# board.net
KiCad netlist of a schematic drawn in EAGLE
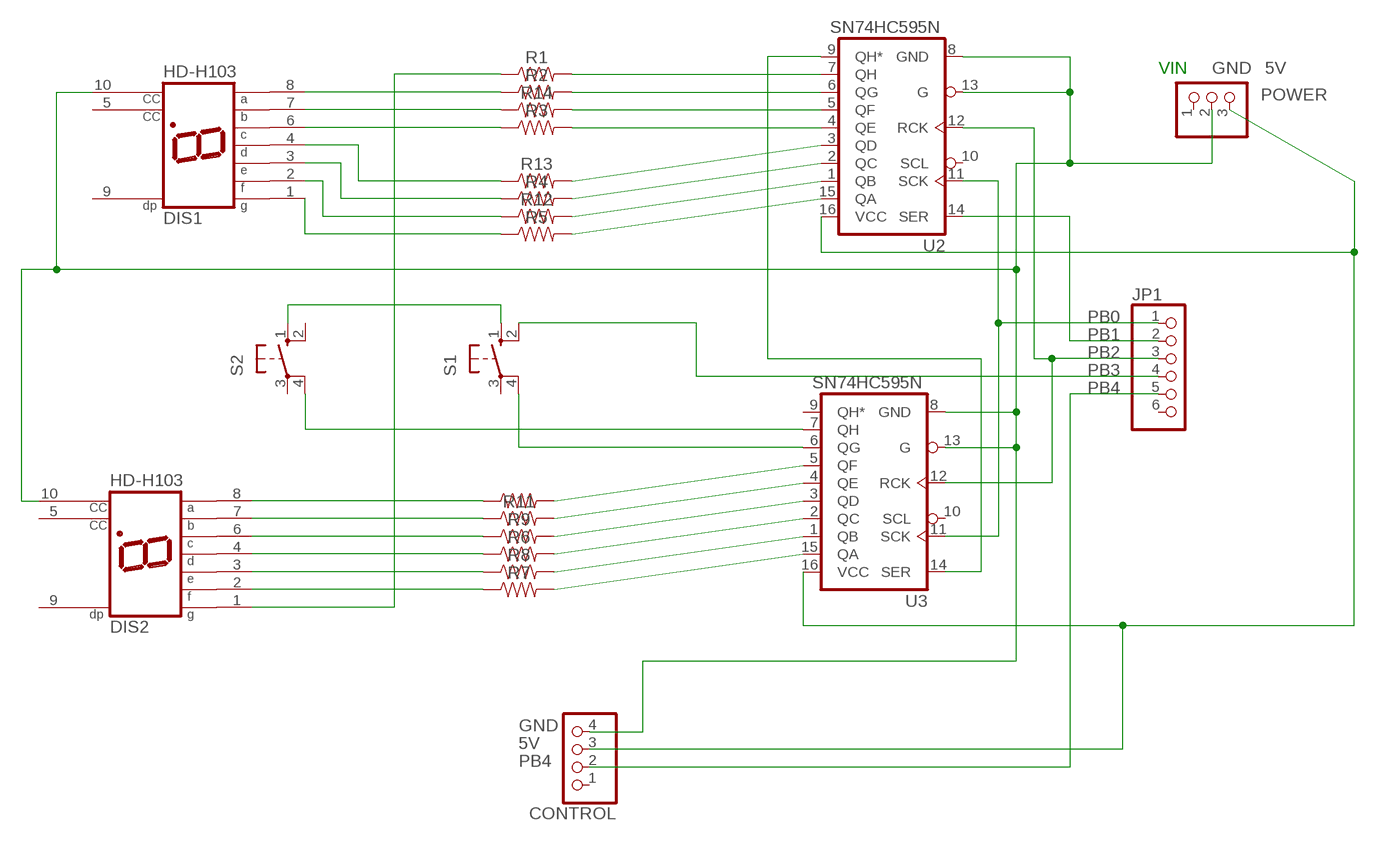
[diagram p0: schematic, sheet 1]

(export (version "E")
  (design (tool "Eeschema 10.0.6"))
  (components
    (comp (ref "CONTROL")
      (value "PINHD-1X4")
      (footprint "eagle-import:1X04")
      (libsource (lib "eagle-import") (part "PINHD-1X4"))
    )
    (comp (ref "DIS1")
      (value "HD-H103")
      (footprint "eagle-import:HDSP-M")
      (libsource (lib "eagle-import") (part "HD-H103"))
    )
    (comp (ref "DIS2")
      (value "HD-H103")
      (footprint "eagle-import:HDSP-M")
      (libsource (lib "eagle-import") (part "HD-H103"))
    )
    (comp (ref "JP1")
      (value "PINHD-1X6")
      (footprint "eagle-import:1X06")
      (libsource (lib "eagle-import") (part "PINHD-1X6"))
    )
    (comp (ref "POWER")
      (value "PINHD-1X3")
      (footprint "eagle-import:1X03")
      (libsource (lib "eagle-import") (part "PINHD-1X3"))
    )
    (comp (ref "R1")
      (value "RESISTORAXIAL-0.3")
      (footprint "eagle-import:AXIAL-0.3")
      (libsource (lib "eagle-import") (part "RESISTORAXIAL-0.3"))
    )
    (comp (ref "R2")
      (value "RESISTORAXIAL-0.3")
      (footprint "eagle-import:AXIAL-0.3")
      (libsource (lib "eagle-import") (part "RESISTORAXIAL-0.3"))
    )
    (comp (ref "R3")
      (value "RESISTORAXIAL-0.3")
      (footprint "eagle-import:AXIAL-0.3")
      (libsource (lib "eagle-import") (part "RESISTORAXIAL-0.3"))
    )
    (comp (ref "R4")
      (value "RESISTORAXIAL-0.3")
      (footprint "eagle-import:AXIAL-0.3")
      (libsource (lib "eagle-import") (part "RESISTORAXIAL-0.3"))
    )
    (comp (ref "R5")
      (value "RESISTORAXIAL-0.3")
      (footprint "eagle-import:AXIAL-0.3")
      (libsource (lib "eagle-import") (part "RESISTORAXIAL-0.3"))
    )
    (comp (ref "R6")
      (value "RESISTORAXIAL-0.3")
      (footprint "eagle-import:AXIAL-0.3")
      (libsource (lib "eagle-import") (part "RESISTORAXIAL-0.3"))
    )
    (comp (ref "R7")
      (value "RESISTORAXIAL-0.3")
      (footprint "eagle-import:AXIAL-0.3")
      (libsource (lib "eagle-import") (part "RESISTORAXIAL-0.3"))
    )
    (comp (ref "R8")
      (value "RESISTORAXIAL-0.3")
      (footprint "eagle-import:AXIAL-0.3")
      (libsource (lib "eagle-import") (part "RESISTORAXIAL-0.3"))
    )
    (comp (ref "R9")
      (value "RESISTORAXIAL-0.3")
      (footprint "eagle-import:AXIAL-0.3")
      (libsource (lib "eagle-import") (part "RESISTORAXIAL-0.3"))
    )
    (comp (ref "R11")
      (value "RESISTORAXIAL-0.3")
      (footprint "eagle-import:AXIAL-0.3")
      (libsource (lib "eagle-import") (part "RESISTORAXIAL-0.3"))
    )
    (comp (ref "R12")
      (value "RESISTORAXIAL-0.3")
      (footprint "eagle-import:AXIAL-0.3")
      (libsource (lib "eagle-import") (part "RESISTORAXIAL-0.3"))
    )
    (comp (ref "R13")
      (value "RESISTORAXIAL-0.3")
      (footprint "eagle-import:AXIAL-0.3")
      (libsource (lib "eagle-import") (part "RESISTORAXIAL-0.3"))
    )
    (comp (ref "R14")
      (value "RESISTORAXIAL-0.3")
      (footprint "eagle-import:AXIAL-0.3")
      (libsource (lib "eagle-import") (part "RESISTORAXIAL-0.3"))
    )
    (comp (ref "R15")
      (value "RESISTORAXIAL-0.3")
      (footprint "eagle-import:AXIAL-0.3")
      (libsource (lib "eagle-import") (part "RESISTORAXIAL-0.3"))
    )
    (comp (ref "S1")
      (value "40-XX")
      (footprint "eagle-import:B3F-40XX")
      (fields (field (name "MF") "OMRON COMPONENTS USA") (field (name "MPN") "B3F-4000"))
      (libsource (lib "eagle-import") (part "40-XX"))
    )
    (comp (ref "S2")
      (value "40-XX")
      (footprint "eagle-import:B3F-40XX")
      (fields (field (name "MF") "OMRON COMPONENTS USA") (field (name "MPN") "B3F-4000"))
      (libsource (lib "eagle-import") (part "40-XX"))
    )
    (comp (ref "U2")
      (value "SN74HC595N")
      (footprint "eagle-import:DIP16")
      (libsource (lib "eagle-import") (part "74595NHC"))
    )
    (comp (ref "U3")
      (value "SN74HC595N")
      (footprint "eagle-import:DIP16")
      (libsource (lib "eagle-import") (part "74595NHC"))
    )
  )
  (nets
    (net (code "1") (name "/5V") (class "Default")
      (node (ref "CONTROL") (pin "3") (pinfunction "3_3") (pintype "passive"))
      (node (ref "POWER") (pin "3") (pinfunction "3_3") (pintype "passive"))
      (node (ref "U2") (pin "16") (pinfunction "VCC_16") (pintype "power_in"))
      (node (ref "U3") (pin "16") (pinfunction "VCC_16") (pintype "power_in"))
    )
    (net (code "2") (name "/GND") (class "Default")
      (node (ref "CONTROL") (pin "4") (pinfunction "4_4") (pintype "passive"))
      (node (ref "DIS1") (pin "10") (pinfunction "CC_10") (pintype "passive"))
      (node (ref "DIS2") (pin "10") (pinfunction "CC_10") (pintype "passive"))
      (node (ref "POWER") (pin "2") (pinfunction "2_2") (pintype "passive"))
      (node (ref "U2") (pin "13") (pinfunction "G_13") (pintype "input"))
      (node (ref "U2") (pin "8") (pinfunction "GND_8") (pintype "power_in"))
      (node (ref "U3") (pin "13") (pinfunction "G_13") (pintype "input"))
      (node (ref "U3") (pin "8") (pinfunction "GND_8") (pintype "power_in"))
    )
    (net (code "3") (name "/PB0") (class "Default")
      (node (ref "JP1") (pin "1") (pinfunction "1_1") (pintype "passive"))
      (node (ref "U2") (pin "11") (pinfunction "SCK_11") (pintype "input"))
      (node (ref "U3") (pin "11") (pinfunction "SCK_11") (pintype "input"))
    )
    (net (code "4") (name "/PB1") (class "Default")
      (node (ref "JP1") (pin "2") (pinfunction "2_2") (pintype "passive"))
      (node (ref "U2") (pin "14") (pinfunction "SER_14") (pintype "input"))
    )
    (net (code "5") (name "/PB2") (class "Default")
      (node (ref "JP1") (pin "3") (pinfunction "3_3") (pintype "passive"))
      (node (ref "U2") (pin "12") (pinfunction "RCK_12") (pintype "input"))
      (node (ref "U3") (pin "12") (pinfunction "RCK_12") (pintype "input"))
    )
    (net (code "6") (name "/PB3") (class "Default")
      (node (ref "JP1") (pin "4") (pinfunction "4_4") (pintype "passive"))
      (node (ref "S1") (pin "2") (pinfunction "S1_2") (pintype "passive"))
    )
    (net (code "7") (name "/PB4") (class "Default")
      (node (ref "CONTROL") (pin "2") (pinfunction "2_2") (pintype "passive"))
      (node (ref "JP1") (pin "5") (pinfunction "5_5") (pintype "passive"))
    )
    (net (code "8") (name "Net-(DIS1-A)") (class "Default")
      (node (ref "DIS1") (pin "3") (pinfunction "A_3") (pintype "passive"))
      (node (ref "R4") (pin "P$1") (pinfunction "1_P$1") (pintype "passive"))
    )
    (net (code "9") (name "Net-(DIS1-B)") (class "Default")
      (node (ref "DIS1") (pin "4") (pinfunction "B_4") (pintype "passive"))
      (node (ref "R13") (pin "P$1") (pinfunction "1_P$1") (pintype "passive"))
    )
    (net (code "10") (name "Net-(DIS1-C)") (class "Default")
      (node (ref "DIS1") (pin "8") (pinfunction "C_8") (pintype "passive"))
      (node (ref "R2") (pin "P$1") (pinfunction "1_P$1") (pintype "passive"))
    )
    (net (code "11") (name "Net-(DIS1-D)") (class "Default")
      (node (ref "DIS1") (pin "7") (pinfunction "D_7") (pintype "passive"))
      (node (ref "R14") (pin "P$1") (pinfunction "1_P$1") (pintype "passive"))
    )
    (net (code "12") (name "Net-(DIS1-E)") (class "Default")
      (node (ref "DIS1") (pin "6") (pinfunction "E_6") (pintype "passive"))
      (node (ref "R3") (pin "P$1") (pinfunction "1_P$1") (pintype "passive"))
    )
    (net (code "13") (name "Net-(DIS1-F)") (class "Default")
      (node (ref "DIS1") (pin "1") (pinfunction "F_1") (pintype "passive"))
      (node (ref "R5") (pin "P$1") (pinfunction "1_P$1") (pintype "passive"))
    )
    (net (code "14") (name "Net-(DIS1-G)") (class "Default")
      (node (ref "DIS1") (pin "2") (pinfunction "G_2") (pintype "passive"))
      (node (ref "R12") (pin "P$1") (pinfunction "1_P$1") (pintype "passive"))
    )
    (net (code "15") (name "Net-(DIS2-A)") (class "Default")
      (node (ref "DIS2") (pin "3") (pinfunction "A_3") (pintype "passive"))
      (node (ref "R8") (pin "P$1") (pinfunction "1_P$1") (pintype "passive"))
    )
    (net (code "16") (name "Net-(DIS2-B)") (class "Default")
      (node (ref "DIS2") (pin "4") (pinfunction "B_4") (pintype "passive"))
      (node (ref "R6") (pin "P$1") (pinfunction "1_P$1") (pintype "passive"))
    )
    (net (code "17") (name "Net-(DIS2-C)") (class "Default")
      (node (ref "DIS2") (pin "8") (pinfunction "C_8") (pintype "passive"))
      (node (ref "R15") (pin "P$1") (pinfunction "1_P$1") (pintype "passive"))
    )
    (net (code "18") (name "Net-(DIS2-D)") (class "Default")
      (node (ref "DIS2") (pin "7") (pinfunction "D_7") (pintype "passive"))
      (node (ref "R11") (pin "P$1") (pinfunction "1_P$1") (pintype "passive"))
    )
    (net (code "19") (name "Net-(DIS2-E)") (class "Default")
      (node (ref "DIS2") (pin "6") (pinfunction "E_6") (pintype "passive"))
      (node (ref "R9") (pin "P$1") (pinfunction "1_P$1") (pintype "passive"))
    )
    (net (code "20") (name "Net-(DIS2-F)") (class "Default")
      (node (ref "DIS2") (pin "1") (pinfunction "F_1") (pintype "passive"))
      (node (ref "R1") (pin "P$1") (pinfunction "1_P$1") (pintype "passive"))
    )
    (net (code "21") (name "Net-(DIS2-G)") (class "Default")
      (node (ref "DIS2") (pin "2") (pinfunction "G_2") (pintype "passive"))
      (node (ref "R7") (pin "P$1") (pinfunction "1_P$1") (pintype "passive"))
    )
    (net (code "22") (name "Net-(R1-2)") (class "Default")
      (node (ref "R1") (pin "P$2") (pinfunction "2_P$2") (pintype "passive"))
      (node (ref "U2") (pin "7") (pinfunction "QH_7") (pintype "tri_state"))
    )
    (net (code "23") (name "Net-(R2-2)") (class "Default")
      (node (ref "R2") (pin "P$2") (pinfunction "2_P$2") (pintype "passive"))
      (node (ref "U2") (pin "6") (pinfunction "QG_6") (pintype "tri_state"))
    )
    (net (code "24") (name "Net-(R3-2)") (class "Default")
      (node (ref "R3") (pin "P$2") (pinfunction "2_P$2") (pintype "passive"))
      (node (ref "U2") (pin "4") (pinfunction "QE_4") (pintype "tri_state"))
    )
    (net (code "25") (name "Net-(R4-2)") (class "Default")
      (node (ref "R4") (pin "P$2") (pinfunction "2_P$2") (pintype "passive"))
      (node (ref "U2") (pin "2") (pinfunction "QC_2") (pintype "tri_state"))
    )
    (net (code "26") (name "Net-(R5-2)") (class "Default")
      (node (ref "R5") (pin "P$2") (pinfunction "2_P$2") (pintype "passive"))
      (node (ref "U2") (pin "15") (pinfunction "QA_15") (pintype "tri_state"))
    )
    (net (code "27") (name "Net-(R6-2)") (class "Default")
      (node (ref "R6") (pin "P$2") (pinfunction "2_P$2") (pintype "passive"))
      (node (ref "U3") (pin "2") (pinfunction "QC_2") (pintype "tri_state"))
    )
    (net (code "28") (name "Net-(R7-2)") (class "Default")
      (node (ref "R7") (pin "P$2") (pinfunction "2_P$2") (pintype "passive"))
      (node (ref "U3") (pin "15") (pinfunction "QA_15") (pintype "tri_state"))
    )
    (net (code "29") (name "Net-(R8-2)") (class "Default")
      (node (ref "R8") (pin "P$2") (pinfunction "2_P$2") (pintype "passive"))
      (node (ref "U3") (pin "1") (pinfunction "QB_1") (pintype "tri_state"))
    )
    (net (code "30") (name "Net-(R9-2)") (class "Default")
      (node (ref "R9") (pin "P$2") (pinfunction "2_P$2") (pintype "passive"))
      (node (ref "U3") (pin "3") (pinfunction "QD_3") (pintype "tri_state"))
    )
    (net (code "31") (name "Net-(R11-2)") (class "Default")
      (node (ref "R11") (pin "P$2") (pinfunction "2_P$2") (pintype "passive"))
      (node (ref "U3") (pin "4") (pinfunction "QE_4") (pintype "tri_state"))
    )
    (net (code "32") (name "Net-(R12-2)") (class "Default")
      (node (ref "R12") (pin "P$2") (pinfunction "2_P$2") (pintype "passive"))
      (node (ref "U2") (pin "1") (pinfunction "QB_1") (pintype "tri_state"))
    )
    (net (code "33") (name "Net-(R13-2)") (class "Default")
      (node (ref "R13") (pin "P$2") (pinfunction "2_P$2") (pintype "passive"))
      (node (ref "U2") (pin "3") (pinfunction "QD_3") (pintype "tri_state"))
    )
    (net (code "34") (name "Net-(R14-2)") (class "Default")
      (node (ref "R14") (pin "P$2") (pinfunction "2_P$2") (pintype "passive"))
      (node (ref "U2") (pin "5") (pinfunction "QF_5") (pintype "tri_state"))
    )
    (net (code "35") (name "Net-(R15-2)") (class "Default")
      (node (ref "R15") (pin "P$2") (pinfunction "2_P$2") (pintype "passive"))
      (node (ref "U3") (pin "5") (pinfunction "QF_5") (pintype "tri_state"))
    )
    (net (code "36") (name "Net-(S1-P1)") (class "Default")
      (node (ref "S1") (pin "4") (pinfunction "P1_4") (pintype "passive"))
      (node (ref "U3") (pin "6") (pinfunction "QG_6") (pintype "tri_state"))
    )
    (net (code "37") (name "Net-(S1-S)") (class "Default")
      (node (ref "S1") (pin "1") (pinfunction "S_1") (pintype "passive"))
      (node (ref "S2") (pin "1") (pinfunction "S_1") (pintype "passive"))
    )
    (net (code "38") (name "Net-(S2-P1)") (class "Default")
      (node (ref "S2") (pin "4") (pinfunction "P1_4") (pintype "passive"))
      (node (ref "U3") (pin "7") (pinfunction "QH_7") (pintype "tri_state"))
    )
    (net (code "39") (name "Net-(U2-QH*)") (class "Default")
      (node (ref "U2") (pin "9") (pinfunction "QH*_9") (pintype "tri_state"))
      (node (ref "U3") (pin "14") (pinfunction "SER_14") (pintype "input"))
    )
    (net (code "40") (name "unconnected-(CONTROL-Pad1)") (class "Default")
      (node (ref "CONTROL") (pin "1") (pinfunction "1_1") (pintype "passive"))
    )
    (net (code "41") (name "unconnected-(DIS1-CC-Pad5)") (class "Default")
      (node (ref "DIS1") (pin "5") (pinfunction "CC_5") (pintype "passive"))
    )
    (net (code "42") (name "unconnected-(DIS1-DP-Pad9)") (class "Default")
      (node (ref "DIS1") (pin "9") (pinfunction "DP_9") (pintype "passive"))
    )
    (net (code "43") (name "unconnected-(DIS2-CC-Pad5)") (class "Default")
      (node (ref "DIS2") (pin "5") (pinfunction "CC_5") (pintype "passive"))
    )
    (net (code "44") (name "unconnected-(DIS2-DP-Pad9)") (class "Default")
      (node (ref "DIS2") (pin "9") (pinfunction "DP_9") (pintype "passive"))
    )
    (net (code "45") (name "unconnected-(JP1-Pad6)") (class "Default")
      (node (ref "JP1") (pin "6") (pinfunction "6_6") (pintype "passive"))
    )
    (net (code "46") (name "unconnected-(POWER-Pad1)") (class "Default")
      (node (ref "POWER") (pin "1") (pinfunction "1_1") (pintype "passive"))
    )
    (net (code "47") (name "unconnected-(S1-P-Pad3)") (class "Default")
      (node (ref "S1") (pin "3") (pinfunction "P_3") (pintype "passive"))
    )
    (net (code "48") (name "unconnected-(S2-P-Pad3)") (class "Default")
      (node (ref "S2") (pin "3") (pinfunction "P_3") (pintype "passive"))
    )
    (net (code "49") (name "unconnected-(S2-S1-Pad2)") (class "Default")
      (node (ref "S2") (pin "2") (pinfunction "S1_2") (pintype "passive"))
    )
    (net (code "50") (name "unconnected-(U2-SCL-Pad10)") (class "Default")
      (node (ref "U2") (pin "10") (pinfunction "SCL_10") (pintype "input"))
    )
    (net (code "51") (name "unconnected-(U3-QH*-Pad9)") (class "Default")
      (node (ref "U3") (pin "9") (pinfunction "QH*_9") (pintype "tri_state"))
    )
    (net (code "52") (name "unconnected-(U3-SCL-Pad10)") (class "Default")
      (node (ref "U3") (pin "10") (pinfunction "SCL_10") (pintype "input"))
    )
  )
)
